# Interfaces.net
KiCad netlist of a schematic drawn in Altium Designer
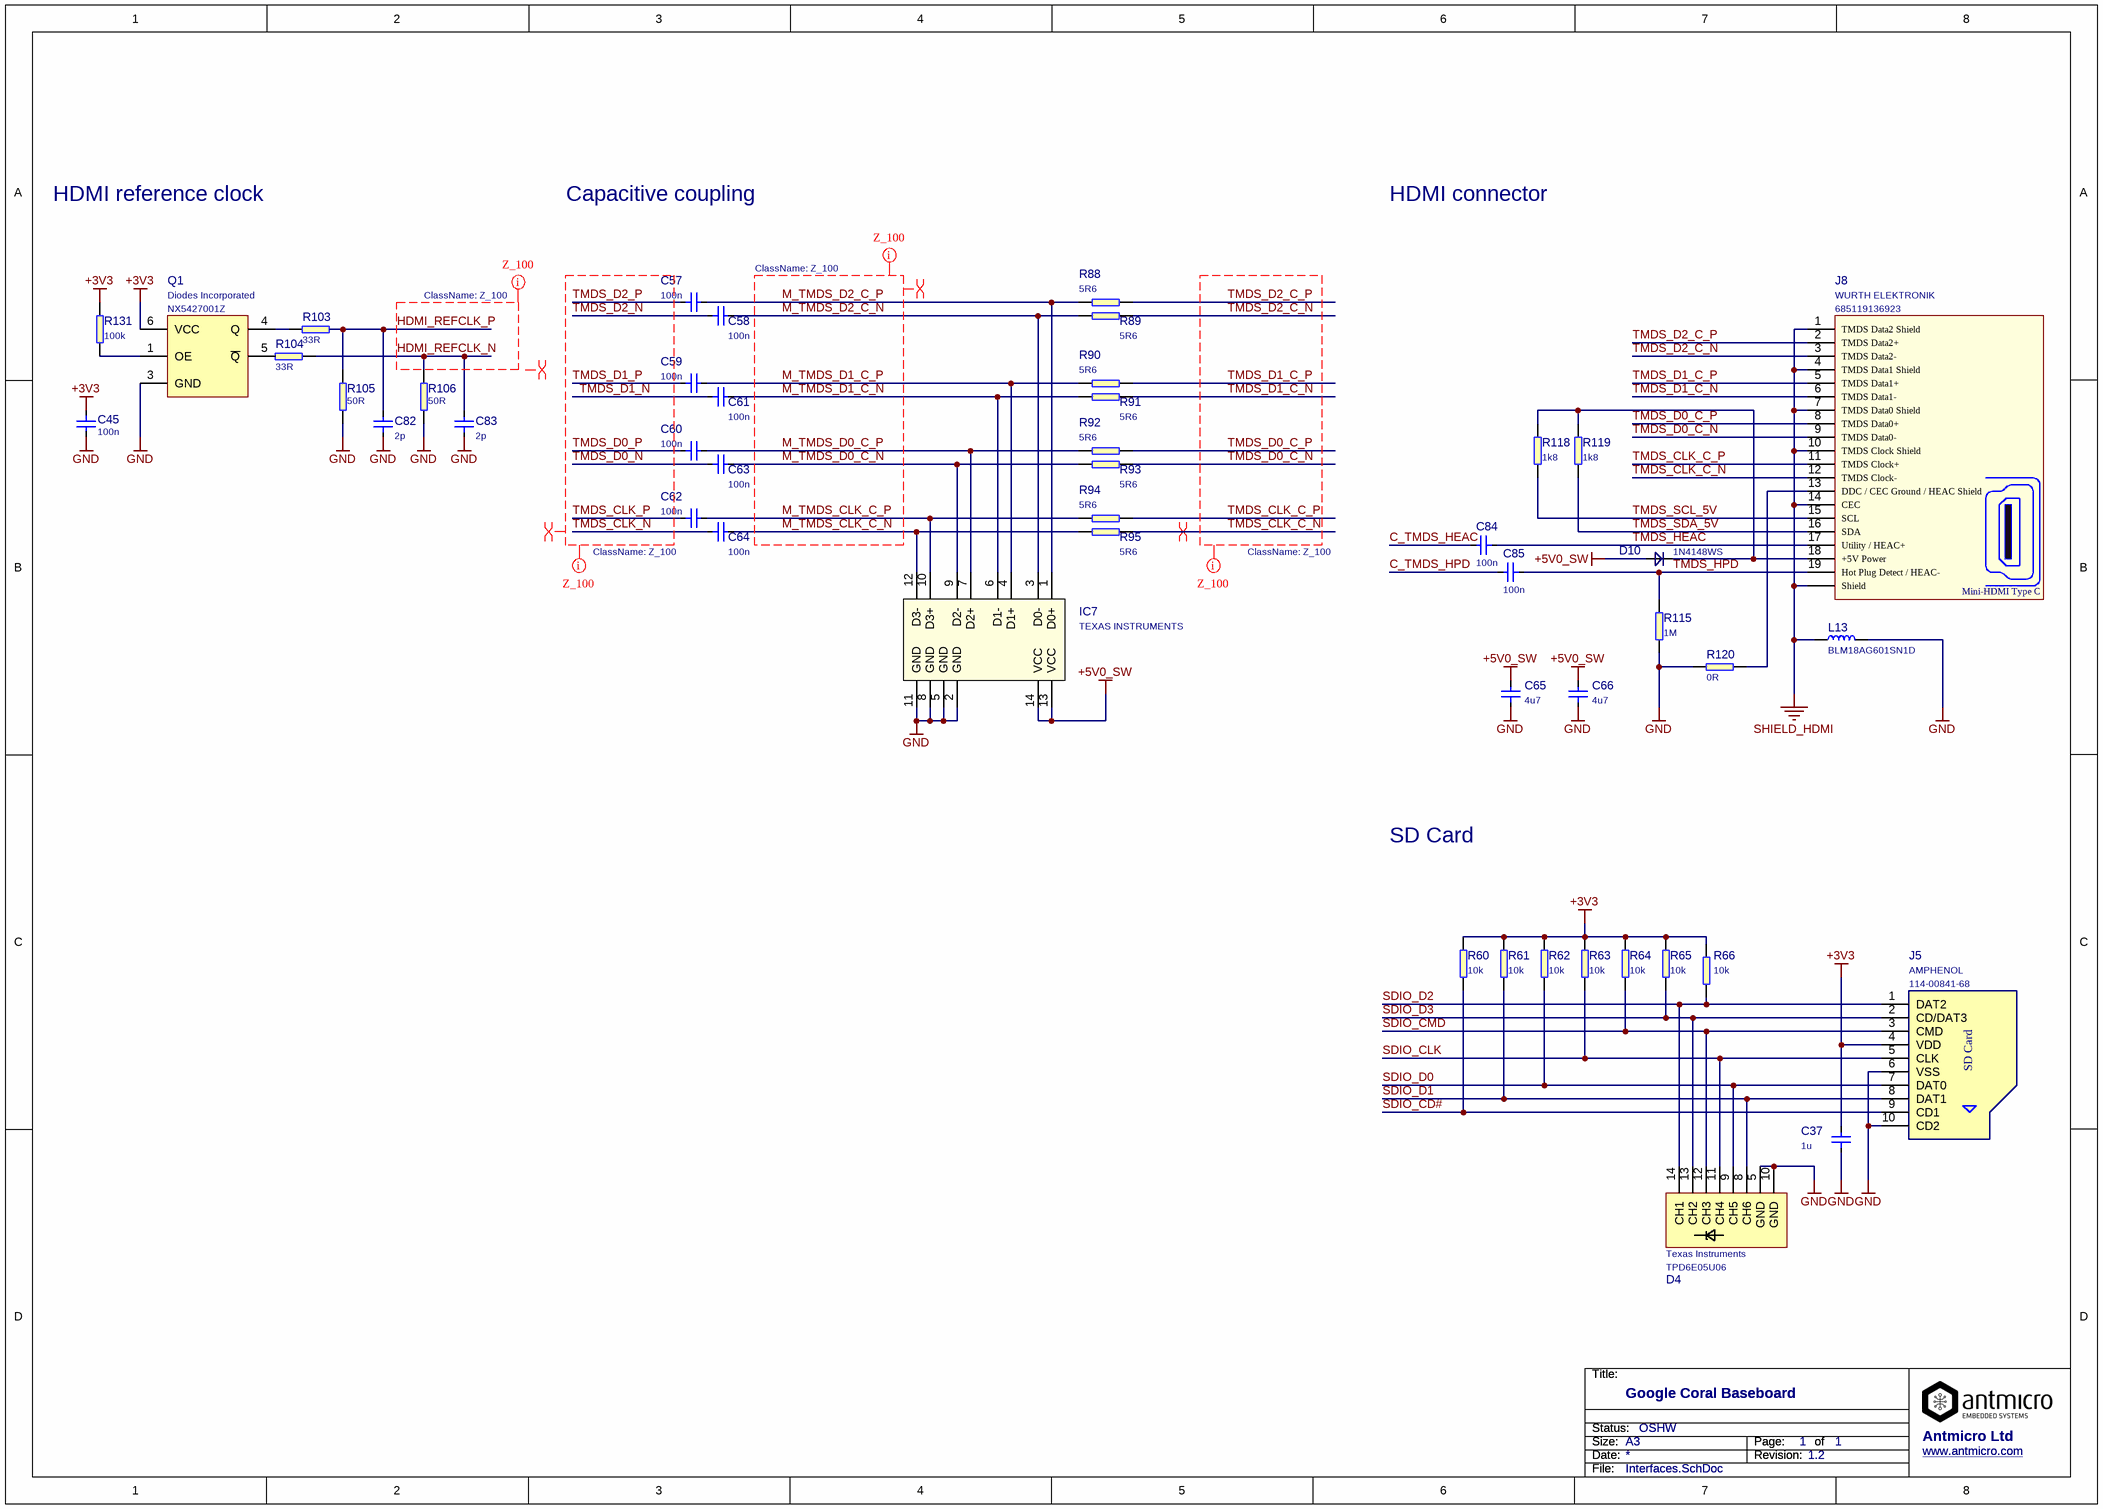
[diagram p0: Interfaces.SchDoc]

(export (version "E")
  (design (tool "Eeschema 10.0.6"))
  (components
    (comp (ref "C37")
      (value "1u")
      (footprint "0603")
      (description "MLCC SMT Capacitor 1uF 0603")
      (fields (field (name "PARTNUMBER") "C_1u_0603"))
      (libsource (lib "altium-import") (part "root_1_C_"))
    )
    (comp (ref "C45")
      (value "100n")
      (footprint "C_0402")
      (description "MLCC SMT Capacitor 100nF 0402")
      (fields (field (name "PARTNUMBER") "C_100n_0402"))
      (libsource (lib "altium-import") (part "root_3_C_"))
    )
    (comp (ref "C57")
      (value "100n")
      (footprint "C_0402")
      (description "MLCC SMT Capacitor 100nF 0402")
      (fields (field (name "PARTNUMBER") "C_100n_0402"))
      (libsource (lib "altium-import") (part "root_0_C_"))
    )
    (comp (ref "C58")
      (value "100n")
      (footprint "C_0402")
      (description "MLCC SMT Capacitor 100nF 0402")
      (fields (field (name "PARTNUMBER") "C_100n_0402"))
      (libsource (lib "altium-import") (part "root_0_C_"))
    )
    (comp (ref "C59")
      (value "100n")
      (footprint "C_0402")
      (description "MLCC SMT Capacitor 100nF 0402")
      (fields (field (name "PARTNUMBER") "C_100n_0402"))
      (libsource (lib "altium-import") (part "root_0_C_"))
    )
    (comp (ref "C60")
      (value "100n")
      (footprint "C_0402")
      (description "MLCC SMT Capacitor 100nF 0402")
      (fields (field (name "PARTNUMBER") "C_100n_0402"))
      (libsource (lib "altium-import") (part "root_0_C_"))
    )
    (comp (ref "C61")
      (value "100n")
      (footprint "C_0402")
      (description "MLCC SMT Capacitor 100nF 0402")
      (fields (field (name "PARTNUMBER") "C_100n_0402"))
      (libsource (lib "altium-import") (part "root_0_C_"))
    )
    (comp (ref "C62")
      (value "100n")
      (footprint "C_0402")
      (description "MLCC SMT Capacitor 100nF 0402")
      (fields (field (name "PARTNUMBER") "C_100n_0402"))
      (libsource (lib "altium-import") (part "root_0_C_"))
    )
    (comp (ref "C63")
      (value "100n")
      (footprint "C_0402")
      (description "MLCC SMT Capacitor 100nF 0402")
      (fields (field (name "PARTNUMBER") "C_100n_0402"))
      (libsource (lib "altium-import") (part "root_0_C_"))
    )
    (comp (ref "C64")
      (value "100n")
      (footprint "C_0402")
      (description "MLCC SMT Capacitor 100nF 0402")
      (fields (field (name "PARTNUMBER") "C_100n_0402"))
      (libsource (lib "altium-import") (part "root_0_C_"))
    )
    (comp (ref "C65")
      (value "4u7")
      (footprint "C_0402")
      (description "MLCC SMT Capacitor 4u7F 0402")
      (fields (field (name "PARTNUMBER") "C_4u7_0402"))
      (libsource (lib "") (part "root_1_C__1"))
    )
    (comp (ref "C66")
      (value "4u7")
      (footprint "C_0402")
      (description "MLCC SMT Capacitor 4u7F 0402")
      (fields (field (name "PARTNUMBER") "C_4u7_0402"))
      (libsource (lib "") (part "root_1_C__1"))
    )
    (comp (ref "C82")
      (value "2p")
      (footprint "C_0402")
      (description "MLCC SMT Capacitor 2p 0402")
      (fields (field (name "PARTNUMBER") "C_2p_0402"))
      (libsource (lib "") (part "root_1_C__1"))
    )
    (comp (ref "C83")
      (value "2p")
      (footprint "C_0402")
      (description "MLCC SMT Capacitor 2p 0402")
      (fields (field (name "PARTNUMBER") "C_2p_0402"))
      (libsource (lib "") (part "root_1_C__1"))
    )
    (comp (ref "C84")
      (value "100n")
      (footprint "C_0402")
      (description "MLCC SMT Capacitor 100nF 0402")
      (fields (field (name "PARTNUMBER") "C_100n_0402"))
      (libsource (lib "altium-import") (part "root_2_C_"))
    )
    (comp (ref "C85")
      (value "100n")
      (footprint "C_0402")
      (description "MLCC SMT Capacitor 100nF 0402")
      (fields (field (name "PARTNUMBER") "C_100n_0402"))
      (libsource (lib "altium-import") (part "root_2_C_"))
    )
    (comp (ref "D4")
      (value "TPD6E05U06")
      (footprint "TPD6E05U06_PASS")
      (description "ESD Suppressors 6-CH Pass through layout")
      (fields (field (name "MANUFACTURER") "Texas Instruments"))
      (libsource (lib "altium-import") (part "root_3_mirrored_TPD6E05U06_"))
    )
    (comp (ref "D10")
      (value "1N4148WS")
      (footprint "SOD-323")
      (description "Diode small signal")
      (fields (field (name "MANUFACTURER") "MULTICOMP"))
      (libsource (lib "altium-import") (part "root_3_diode_"))
    )
    (comp (ref "IC7")
      (value "TPD8S009")
      (footprint "SON-15")
      (description "8-Channel ESD Protection for DisplayPort and HDMI")
      (fields (field (name "MANUFACTURER") "TEXAS INSTRUMENTS"))
      (libsource (lib "altium-import") (part "root_3_TPD8S009_"))
    )
    (comp (ref "J5")
      (value "114-00841-68")
      (footprint "114-00841-68")
      (description "Micro SD card holder")
      (fields (field (name "MANUFACTURER") "AMPHENOL") (field (name "PARTNUMBER") "114-00841-68"))
      (libsource (lib "altium-import") (part "root_0_Micro_SD_"))
    )
    (comp (ref "J8")
      (value "685119136923")
      (footprint "WE_685119136923")
      (description "CONN HDMI FEMALE R/A 19POS 2.6MM")
      (fields (field (name "PARTNUMBER") "WE_685119136923") (field (name "MANUFACTURER") "WURTH ELEKTRONIK"))
      (libsource (lib "altium-import") (part "root_0_WE_685119136923_"))
    )
    (comp (ref "L13")
      (value "BLM18AG601SN1D")
      (footprint "0603")
      (description "Ferrite Bead, 600 ohm, 0603 [1608 Metric], BLM18A Series, 500 mA, 0.38 ohm, ? 25%")
      (fields (field (name "MANUFACTURER") "MURATA"))
      (libsource (lib "altium-import") (part "root_0_Inductor SMT_"))
    )
    (comp (ref "Q1")
      (value "NX5427001Z")
      (footprint "NX5427001Z")
      (description "CLOCK SAW OSCILLATOR SEAM5032")
      (fields (field (name "PARTNUMBER") "NX5427001Z") (field (name "MANUFACTURER") "Diodes Incorporated"))
      (libsource (lib "altium-import") (part "root_0_NX5427001Z_"))
    )
    (comp (ref "R60")
      (value "10k")
      (footprint "0402")
      (description "SMT Resistor 0402")
      (fields (field (name "PARTNUMBER") "R_10k_0402"))
      (libsource (lib "altium-import") (part "root_1_R_"))
    )
    (comp (ref "R61")
      (value "10k")
      (footprint "0402")
      (description "SMT Resistor 0402")
      (fields (field (name "PARTNUMBER") "R_10k_0402"))
      (libsource (lib "altium-import") (part "root_1_R_"))
    )
    (comp (ref "R62")
      (value "10k")
      (footprint "0402")
      (description "SMT Resistor 0402")
      (fields (field (name "PARTNUMBER") "R_10k_0402"))
      (libsource (lib "altium-import") (part "root_1_R_"))
    )
    (comp (ref "R63")
      (value "10k")
      (footprint "0402")
      (description "SMT Resistor 0402")
      (fields (field (name "PARTNUMBER") "R_10k_0402"))
      (libsource (lib "altium-import") (part "root_1_R_"))
    )
    (comp (ref "R64")
      (value "10k")
      (footprint "0402")
      (description "SMT Resistor 0402")
      (fields (field (name "PARTNUMBER") "R_10k_0402"))
      (libsource (lib "altium-import") (part "root_1_R_"))
    )
    (comp (ref "R65")
      (value "10k")
      (footprint "0402")
      (description "SMT Resistor 0402")
      (fields (field (name "PARTNUMBER") "R_10k_0402"))
      (libsource (lib "altium-import") (part "root_1_R_"))
    )
    (comp (ref "R66")
      (value "10k")
      (footprint "0402")
      (description "SMT Resistor 0402")
      (fields (field (name "PARTNUMBER") "R_10k_0402"))
      (libsource (lib "altium-import") (part "root_1_R_"))
    )
    (comp (ref "R88")
      (value "5R6")
      (footprint "0402")
      (description "SMD Resistor 0402")
      (fields (field (name "PARTNUMBER") "R_5R6_0402"))
      (libsource (lib "altium-import") (part "root_0_R_"))
    )
    (comp (ref "R89")
      (value "5R6")
      (footprint "0402")
      (description "SMD Resistor 0402")
      (fields (field (name "PARTNUMBER") "R_5R6_0402"))
      (libsource (lib "altium-import") (part "root_0_R_"))
    )
    (comp (ref "R90")
      (value "5R6")
      (footprint "0402")
      (description "SMD Resistor 0402")
      (fields (field (name "PARTNUMBER") "R_5R6_0402"))
      (libsource (lib "altium-import") (part "root_0_R_"))
    )
    (comp (ref "R91")
      (value "5R6")
      (footprint "0402")
      (description "SMD Resistor 0402")
      (fields (field (name "PARTNUMBER") "R_5R6_0402"))
      (libsource (lib "altium-import") (part "root_0_R_"))
    )
    (comp (ref "R92")
      (value "5R6")
      (footprint "0402")
      (description "SMD Resistor 0402")
      (fields (field (name "PARTNUMBER") "R_5R6_0402"))
      (libsource (lib "altium-import") (part "root_0_R_"))
    )
    (comp (ref "R93")
      (value "5R6")
      (footprint "0402")
      (description "SMD Resistor 0402")
      (fields (field (name "PARTNUMBER") "R_5R6_0402"))
      (libsource (lib "altium-import") (part "root_0_R_"))
    )
    (comp (ref "R94")
      (value "5R6")
      (footprint "0402")
      (description "SMD Resistor 0402")
      (fields (field (name "PARTNUMBER") "R_5R6_0402"))
      (libsource (lib "altium-import") (part "root_0_R_"))
    )
    (comp (ref "R95")
      (value "5R6")
      (footprint "0402")
      (description "SMD Resistor 0402")
      (fields (field (name "PARTNUMBER") "R_5R6_0402"))
      (libsource (lib "altium-import") (part "root_0_R_"))
    )
    (comp (ref "R103")
      (value "33R")
      (footprint "0402")
      (description "RES, 33R, 0402, 1%")
      (fields (field (name "PARTNUMBER") "R_33R_0402"))
      (libsource (lib "altium-import") (part "root_0_R_"))
    )
    (comp (ref "R104")
      (value "33R")
      (footprint "0402")
      (description "RES, 33R, 0402, 1%")
      (fields (field (name "PARTNUMBER") "R_33R_0402"))
      (libsource (lib "altium-import") (part "root_0_R_"))
    )
    (comp (ref "R105")
      (value "50R")
      (footprint "0402")
      (description "RES, 33R, 0402, 1%")
      (fields (field (name "PARTNUMBER") "R_50R_0402"))
      (libsource (lib "altium-import") (part "root_1_R_"))
    )
    (comp (ref "R106")
      (value "50R")
      (footprint "0402")
      (description "RES, 33R, 0402, 1%")
      (fields (field (name "PARTNUMBER") "R_50R_0402"))
      (libsource (lib "altium-import") (part "root_1_R_"))
    )
    (comp (ref "R115")
      (value "1M")
      (footprint "0402")
      (description "SMT Resistor 1M 0402")
      (fields (field (name "PARTNUMBER") "R_1M_0402"))
      (libsource (lib "altium-import") (part "root_1_R_"))
    )
    (comp (ref "R118")
      (value "1k8")
      (footprint "0603")
      (description "SMT Resistor 1k8 0603")
      (fields (field (name "PARTNUMBER") "R_1k8_0603"))
      (libsource (lib "altium-import") (part "root_1_R_"))
    )
    (comp (ref "R119")
      (value "1k8")
      (footprint "0603")
      (description "SMT Resistor 1k8 0603")
      (fields (field (name "PARTNUMBER") "R_1k8_0603"))
      (libsource (lib "altium-import") (part "root_1_R_"))
    )
    (comp (ref "R120")
      (value "0R")
      (footprint "0402")
      (description "SMT Resistor 0402")
      (fields (field (name "PARTNUMBER") "R_0R_0402"))
      (libsource (lib "altium-import") (part "root_0_R_"))
    )
    (comp (ref "R131")
      (value "100k")
      (footprint "0402")
      (description "SMT Resistor 100k 0402")
      (fields (field (name "PARTNUMBER") "R_100k_0402"))
      (libsource (lib "altium-import") (part "root_1_R_"))
    )
  )
  (nets
    (net (code "1") (name "+3V3") (class "Default")
      (node (ref "C37") (pin "2") (pinfunction "2_2") (pintype "passive"))
      (node (ref "C45") (pin "1") (pinfunction "1_1") (pintype "passive"))
      (node (ref "J5") (pin "4") (pinfunction "VDD_4") (pintype "passive"))
      (node (ref "Q1") (pin "6") (pinfunction "VCC_6") (pintype "passive"))
      (node (ref "R131") (pin "2") (pintype "passive"))
      (node (ref "R60") (pin "2") (pintype "passive"))
      (node (ref "R61") (pin "2") (pintype "passive"))
      (node (ref "R62") (pin "2") (pintype "passive"))
      (node (ref "R63") (pin "2") (pintype "passive"))
      (node (ref "R64") (pin "2") (pintype "passive"))
      (node (ref "R65") (pin "2") (pintype "passive"))
      (node (ref "R66") (pin "2") (pintype "passive"))
    )
    (net (code "2") (name "+5V0_SW") (class "Default")
      (node (ref "C65") (pin "2") (pinfunction "2_2") (pintype "passive"))
      (node (ref "C66") (pin "2") (pinfunction "2_2") (pintype "passive"))
      (node (ref "D10") (pin "A") (pinfunction "A_A") (pintype "passive"))
      (node (ref "IC7") (pin "13") (pinfunction "VCC_13") (pintype "passive"))
      (node (ref "IC7") (pin "14") (pinfunction "VCC_14") (pintype "passive"))
    )
    (net (code "3") (name "/C_TMDS_HEAC") (class "Default")
      (node (ref "C84") (pin "2") (pinfunction "2_2") (pintype "passive"))
    )
    (net (code "4") (name "/C_TMDS_HPD") (class "Default")
      (node (ref "C85") (pin "2") (pinfunction "2_2") (pintype "passive"))
    )
    (net (code "5") (name "/HDMI_REFCLK_N") (class "Default")
      (node (ref "C83") (pin "2") (pinfunction "2_2") (pintype "passive"))
      (node (ref "R104") (pin "2") (pintype "passive"))
      (node (ref "R106") (pin "2") (pintype "passive"))
    )
    (net (code "6") (name "/HDMI_REFCLK_P") (class "Default")
      (node (ref "C82") (pin "2") (pinfunction "2_2") (pintype "passive"))
      (node (ref "R103") (pin "2") (pintype "passive"))
      (node (ref "R105") (pin "2") (pintype "passive"))
    )
    (net (code "7") (name "/M_TMDS_CLK_C_N") (class "Default")
      (node (ref "C64") (pin "2") (pinfunction "2_2") (pintype "passive"))
      (node (ref "IC7") (pin "12") (pinfunction "D3-_12") (pintype "passive"))
      (node (ref "R95") (pin "1") (pintype "passive"))
    )
    (net (code "8") (name "/M_TMDS_CLK_C_P") (class "Default")
      (node (ref "C62") (pin "2") (pinfunction "2_2") (pintype "passive"))
      (node (ref "IC7") (pin "10") (pinfunction "D3+_10") (pintype "passive"))
      (node (ref "R94") (pin "1") (pintype "passive"))
    )
    (net (code "9") (name "/M_TMDS_D0_C_N") (class "Default")
      (node (ref "C63") (pin "2") (pinfunction "2_2") (pintype "passive"))
      (node (ref "IC7") (pin "9") (pinfunction "D2-_9") (pintype "passive"))
      (node (ref "R93") (pin "1") (pintype "passive"))
    )
    (net (code "10") (name "/M_TMDS_D0_C_P") (class "Default")
      (node (ref "C60") (pin "2") (pinfunction "2_2") (pintype "passive"))
      (node (ref "IC7") (pin "7") (pinfunction "D2+_7") (pintype "passive"))
      (node (ref "R92") (pin "1") (pintype "passive"))
    )
    (net (code "11") (name "/M_TMDS_D1_C_N") (class "Default")
      (node (ref "C61") (pin "2") (pinfunction "2_2") (pintype "passive"))
      (node (ref "IC7") (pin "6") (pinfunction "D1-_6") (pintype "passive"))
      (node (ref "R91") (pin "1") (pintype "passive"))
    )
    (net (code "12") (name "/M_TMDS_D1_C_P") (class "Default")
      (node (ref "C59") (pin "2") (pinfunction "2_2") (pintype "passive"))
      (node (ref "IC7") (pin "4") (pinfunction "D1+_4") (pintype "passive"))
      (node (ref "R90") (pin "1") (pintype "passive"))
    )
    (net (code "13") (name "/M_TMDS_D2_C_N") (class "Default")
      (node (ref "C58") (pin "2") (pinfunction "2_2") (pintype "passive"))
      (node (ref "IC7") (pin "3") (pinfunction "D0-_3") (pintype "passive"))
      (node (ref "R89") (pin "1") (pintype "passive"))
    )
    (net (code "14") (name "/M_TMDS_D2_C_P") (class "Default")
      (node (ref "C57") (pin "2") (pinfunction "2_2") (pintype "passive"))
      (node (ref "IC7") (pin "1") (pinfunction "D0+_1") (pintype "passive"))
      (node (ref "R88") (pin "1") (pintype "passive"))
    )
    (net (code "15") (name "/SDIO_CD#") (class "Default")
      (node (ref "J5") (pin "9") (pinfunction "CD1_9") (pintype "passive"))
      (node (ref "R60") (pin "1") (pintype "passive"))
    )
    (net (code "16") (name "/SDIO_CLK") (class "Default")
      (node (ref "D4") (pin "11") (pinfunction "CH4_11") (pintype "passive"))
      (node (ref "J5") (pin "5") (pinfunction "CLK_5") (pintype "passive"))
      (node (ref "R63") (pin "1") (pintype "passive"))
    )
    (net (code "17") (name "/SDIO_CMD") (class "Default")
      (node (ref "D4") (pin "12") (pinfunction "CH3_12") (pintype "passive"))
      (node (ref "J5") (pin "3") (pinfunction "CMD_3") (pintype "passive"))
      (node (ref "R64") (pin "1") (pintype "passive"))
    )
    (net (code "18") (name "/SDIO_D0") (class "Default")
      (node (ref "D4") (pin "9") (pinfunction "CH5_9") (pintype "passive"))
      (node (ref "J5") (pin "7") (pinfunction "DAT0_7") (pintype "passive"))
      (node (ref "R62") (pin "1") (pintype "passive"))
    )
    (net (code "19") (name "/SDIO_D1") (class "Default")
      (node (ref "D4") (pin "8") (pinfunction "CH6_8") (pintype "passive"))
      (node (ref "J5") (pin "8") (pinfunction "DAT1_8") (pintype "passive"))
      (node (ref "R61") (pin "1") (pintype "passive"))
    )
    (net (code "20") (name "/SDIO_D2") (class "Default")
      (node (ref "D4") (pin "14") (pinfunction "CH1_14") (pintype "passive"))
      (node (ref "J5") (pin "1") (pinfunction "DAT2_1") (pintype "passive"))
      (node (ref "R66") (pin "1") (pintype "passive"))
    )
    (net (code "21") (name "/SDIO_D3") (class "Default")
      (node (ref "D4") (pin "13") (pinfunction "CH2_13") (pintype "passive"))
      (node (ref "J5") (pin "2") (pinfunction "CD/DAT3_2") (pintype "passive"))
      (node (ref "R65") (pin "1") (pintype "passive"))
    )
    (net (code "22") (name "/TMDS_CLK_C_N") (class "Default")
      (node (ref "J8") (pin "12") (pinfunction "TMDS_Clock-_12") (pintype "passive"))
      (node (ref "R95") (pin "2") (pintype "passive"))
    )
    (net (code "23") (name "/TMDS_CLK_C_P") (class "Default")
      (node (ref "J8") (pin "11") (pinfunction "TMDS_Clock+_11") (pintype "passive"))
      (node (ref "R94") (pin "2") (pintype "passive"))
    )
    (net (code "24") (name "/TMDS_CLK_N") (class "Default")
      (node (ref "C64") (pin "1") (pinfunction "1_1") (pintype "passive"))
    )
    (net (code "25") (name "/TMDS_CLK_P") (class "Default")
      (node (ref "C62") (pin "1") (pinfunction "1_1") (pintype "passive"))
    )
    (net (code "26") (name "/TMDS_D0_C_N") (class "Default")
      (node (ref "J8") (pin "9") (pinfunction "TMDS_Data0-_9") (pintype "passive"))
      (node (ref "R93") (pin "2") (pintype "passive"))
    )
    (net (code "27") (name "/TMDS_D0_C_P") (class "Default")
      (node (ref "J8") (pin "8") (pinfunction "TMDS_Data0+_8") (pintype "passive"))
      (node (ref "R92") (pin "2") (pintype "passive"))
    )
    (net (code "28") (name "/TMDS_D0_N") (class "Default")
      (node (ref "C63") (pin "1") (pinfunction "1_1") (pintype "passive"))
    )
    (net (code "29") (name "/TMDS_D0_P") (class "Default")
      (node (ref "C60") (pin "1") (pinfunction "1_1") (pintype "passive"))
    )
    (net (code "30") (name "/TMDS_D1_C_N") (class "Default")
      (node (ref "J8") (pin "6") (pinfunction "TMDS_Data1-_6") (pintype "passive"))
      (node (ref "R91") (pin "2") (pintype "passive"))
    )
    (net (code "31") (name "/TMDS_D1_C_P") (class "Default")
      (node (ref "J8") (pin "5") (pinfunction "TMDS_Data1+_5") (pintype "passive"))
      (node (ref "R90") (pin "2") (pintype "passive"))
    )
    (net (code "32") (name "/TMDS_D1_N") (class "Default")
      (node (ref "C61") (pin "1") (pinfunction "1_1") (pintype "passive"))
    )
    (net (code "33") (name "/TMDS_D1_P") (class "Default")
      (node (ref "C59") (pin "1") (pinfunction "1_1") (pintype "passive"))
    )
    (net (code "34") (name "/TMDS_D2_C_N") (class "Default")
      (node (ref "J8") (pin "3") (pinfunction "TMDS_Data2-_3") (pintype "passive"))
      (node (ref "R89") (pin "2") (pintype "passive"))
    )
    (net (code "35") (name "/TMDS_D2_C_P") (class "Default")
      (node (ref "J8") (pin "2") (pinfunction "TMDS_Data2+_2") (pintype "passive"))
      (node (ref "R88") (pin "2") (pintype "passive"))
    )
    (net (code "36") (name "/TMDS_D2_N") (class "Default")
      (node (ref "C58") (pin "1") (pinfunction "1_1") (pintype "passive"))
    )
    (net (code "37") (name "/TMDS_D2_P") (class "Default")
      (node (ref "C57") (pin "1") (pinfunction "1_1") (pintype "passive"))
    )
    (net (code "38") (name "/TMDS_HEAC") (class "Default")
      (node (ref "C84") (pin "1") (pinfunction "1_1") (pintype "passive"))
      (node (ref "J8") (pin "17") (pinfunction "Utility_/_HEAC+_17") (pintype "passive"))
    )
    (net (code "39") (name "/TMDS_HPD") (class "Default")
      (node (ref "C85") (pin "1") (pinfunction "1_1") (pintype "passive"))
      (node (ref "J8") (pin "19") (pinfunction "Hot_Plug_Detect_/_HEAC-_19") (pintype "passive"))
      (node (ref "R115") (pin "2") (pintype "passive"))
    )
    (net (code "40") (name "/TMDS_SCL_5V") (class "Default")
      (node (ref "J8") (pin "15") (pinfunction "SCL_15") (pintype "passive"))
      (node (ref "R118") (pin "1") (pintype "passive"))
    )
    (net (code "41") (name "/TMDS_SDA_5V") (class "Default")
      (node (ref "J8") (pin "16") (pinfunction "SDA_16") (pintype "passive"))
      (node (ref "R119") (pin "1") (pintype "passive"))
    )
    (net (code "42") (name "GND") (class "Default")
      (node (ref "C37") (pin "1") (pinfunction "1_1") (pintype "passive"))
      (node (ref "C45") (pin "2") (pinfunction "2_2") (pintype "passive"))
      (node (ref "C65") (pin "1") (pinfunction "1_1") (pintype "passive"))
      (node (ref "C66") (pin "1") (pinfunction "1_1") (pintype "passive"))
      (node (ref "C82") (pin "1") (pinfunction "1_1") (pintype "passive"))
      (node (ref "C83") (pin "1") (pinfunction "1_1") (pintype "passive"))
      (node (ref "D4") (pin "10") (pinfunction "GND_10") (pintype "passive"))
      (node (ref "D4") (pin "5") (pinfunction "GND_5") (pintype "passive"))
      (node (ref "IC7") (pin "11") (pinfunction "GND_11") (pintype "passive"))
      (node (ref "IC7") (pin "2") (pinfunction "GND_2") (pintype "passive"))
      (node (ref "IC7") (pin "5") (pinfunction "GND_5") (pintype "passive"))
      (node (ref "IC7") (pin "8") (pinfunction "GND_8") (pintype "passive"))
      (node (ref "J5") (pin "10") (pinfunction "CD2_10") (pintype "passive"))
      (node (ref "J5") (pin "6") (pinfunction "VSS_6") (pintype "passive"))
      (node (ref "L13") (pin "2") (pintype "passive"))
      (node (ref "Q1") (pin "3") (pinfunction "GND_3") (pintype "passive"))
      (node (ref "R105") (pin "1") (pintype "passive"))
      (node (ref "R106") (pin "1") (pintype "passive"))
      (node (ref "R115") (pin "1") (pintype "passive"))
      (node (ref "R120") (pin "1") (pintype "passive"))
    )
    (net (code "43") (name "Net-(J8-+5V_Power)") (class "Default")
      (node (ref "D10") (pin "C") (pinfunction "C_C") (pintype "passive"))
      (node (ref "J8") (pin "18") (pinfunction "+5V_Power_18") (pintype "passive"))
      (node (ref "R118") (pin "2") (pintype "passive"))
      (node (ref "R119") (pin "2") (pintype "passive"))
    )
    (net (code "44") (name "Net-(J8-DDC_{slash}_CEC_Ground_{slash}_HEAC_Shield)") (class "Default")
      (node (ref "J8") (pin "13") (pinfunction "DDC_/_CEC_Ground_/_HEAC_Shield_13") (pintype "passive"))
      (node (ref "R120") (pin "2") (pintype "passive"))
    )
    (net (code "45") (name "Net-(Q1-OE)") (class "Default")
      (node (ref "Q1") (pin "1") (pinfunction "OE_1") (pintype "passive"))
      (node (ref "R131") (pin "1") (pintype "passive"))
    )
    (net (code "46") (name "Net-(Q1-Q)") (class "Default")
      (node (ref "Q1") (pin "4") (pinfunction "Q_4") (pintype "passive"))
      (node (ref "R103") (pin "1") (pintype "passive"))
    )
    (net (code "47") (name "Net-(Q1-~{Q})") (class "Default")
      (node (ref "Q1") (pin "5") (pinfunction "~{Q}_5") (pintype "passive"))
      (node (ref "R104") (pin "1") (pintype "passive"))
    )
    (net (code "48") (name "SHIELD_HDMI") (class "Default")
      (node (ref "J8") (pin "1") (pinfunction "TMDS_Data2_Shield_1") (pintype "passive"))
      (node (ref "J8") (pin "10") (pinfunction "TMDS_Clock_Shield_10") (pintype "passive"))
      (node (ref "J8") (pin "14") (pinfunction "CEC_14") (pintype "passive"))
      (node (ref "J8") (pin "4") (pinfunction "TMDS_Data1_Shield_4") (pintype "passive"))
      (node (ref "J8") (pin "7") (pinfunction "TMDS_Data0_Shield_7") (pintype "passive"))
      (node (ref "J8") (pin "Shell") (pinfunction "Shield_Shell") (pintype "passive"))
      (node (ref "L13") (pin "1") (pintype "passive"))
    )
  )
)
